# control_board_final.net
KiCad netlist of a schematic drawn in EAGLE
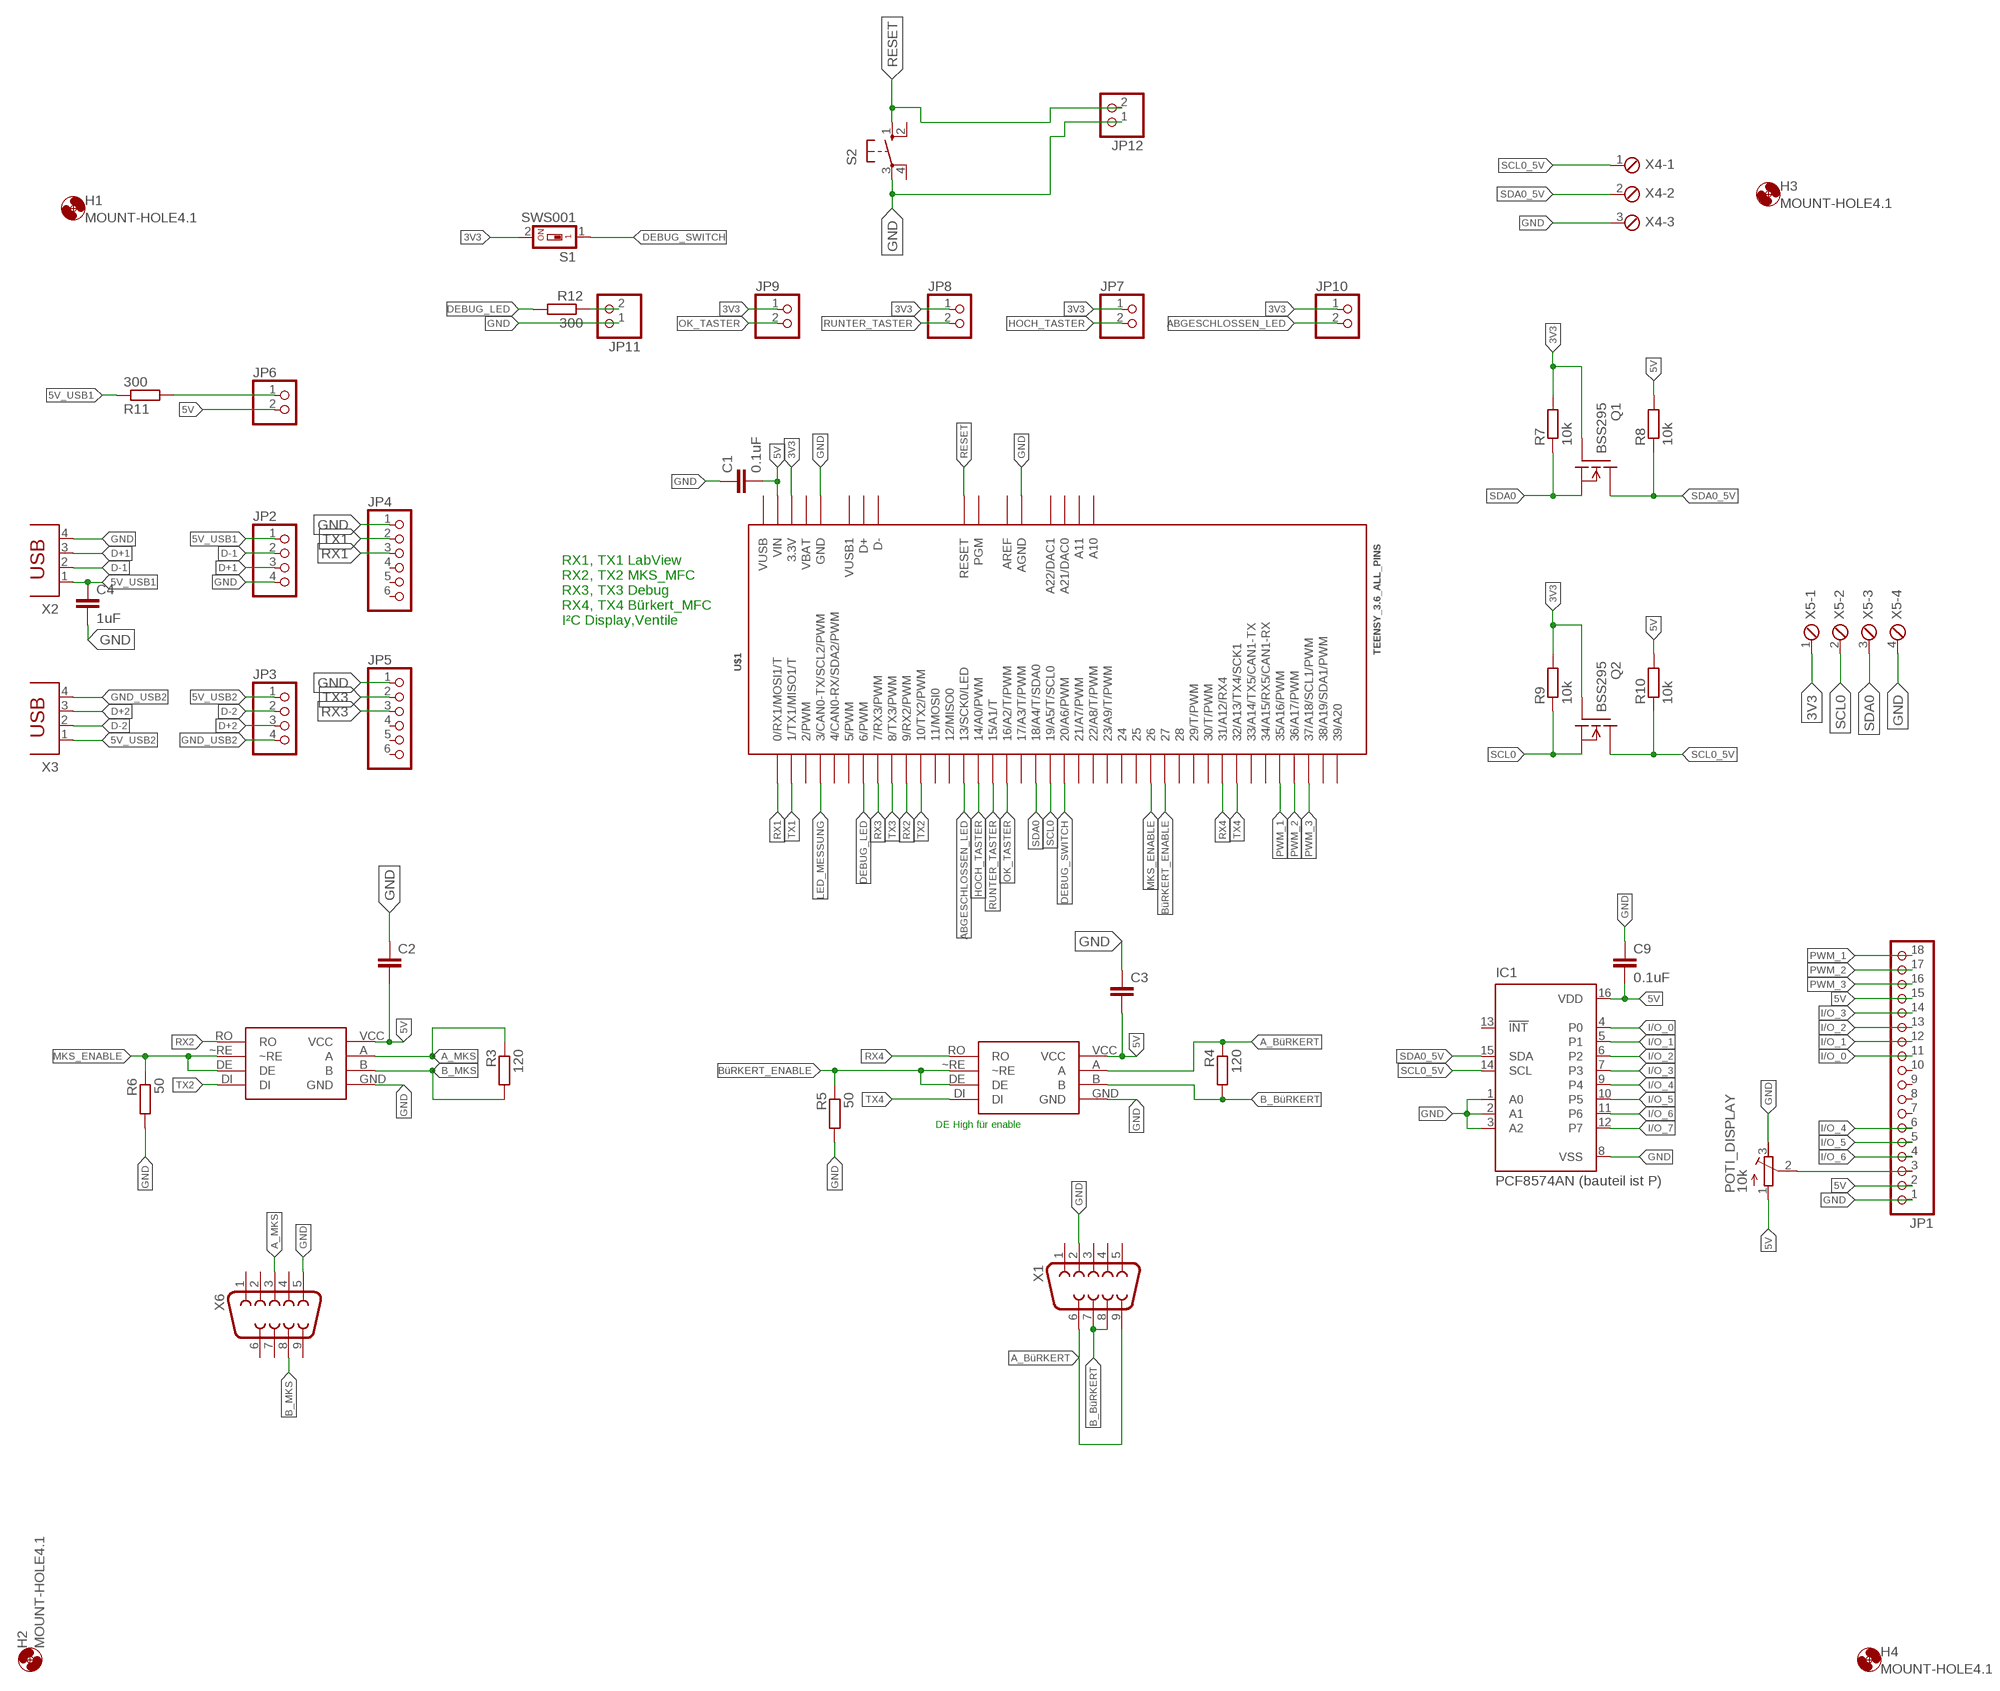
[diagram p0: schematic, sheet 1]

(export (version "E")
  (design (tool "Eeschema 10.0.6"))
  (components
    (comp (ref "C1")
      (value "0.1uF")
      (footprint "eagle-import:C0805")
      (libsource (lib "eagle-import") (part "C-EUC0805"))
    )
    (comp (ref "C2")
      (value "C-EUC0805")
      (footprint "eagle-import:C0805")
      (libsource (lib "eagle-import") (part "C-EUC0805"))
    )
    (comp (ref "C3")
      (value "C-EUC0805")
      (footprint "eagle-import:C0805")
      (libsource (lib "eagle-import") (part "C-EUC0805"))
    )
    (comp (ref "C4")
      (value "1uF")
      (footprint "eagle-import:C0805")
      (libsource (lib "eagle-import") (part "C-EUC0805"))
    )
    (comp (ref "C9")
      (value "0.1uF")
      (footprint "eagle-import:C0805")
      (libsource (lib "eagle-import") (part "C-EUC0805"))
    )
    (comp (ref "H1")
      (value "MOUNT-HOLE4.1")
      (footprint "eagle-import:4,1")
      (libsource (lib "eagle-import") (part "MOUNT-HOLE4.1"))
    )
    (comp (ref "H2")
      (value "MOUNT-HOLE4.1")
      (footprint "eagle-import:4,1")
      (libsource (lib "eagle-import") (part "MOUNT-HOLE4.1"))
    )
    (comp (ref "H3")
      (value "MOUNT-HOLE4.1")
      (footprint "eagle-import:4,1")
      (libsource (lib "eagle-import") (part "MOUNT-HOLE4.1"))
    )
    (comp (ref "H4")
      (value "MOUNT-HOLE4.1")
      (footprint "eagle-import:4,1")
      (libsource (lib "eagle-import") (part "MOUNT-HOLE4.1"))
    )
    (comp (ref "IC1")
      (value "PCF8574AN (bauteil ist P)")
      (footprint "eagle-import:DIL16")
      (fields (field (name "MPN") "PCF8574PN"))
      (libsource (lib "eagle-import") (part "PCF8574P"))
    )
    (comp (ref "JP1")
      (value "PINHD-1X18")
      (footprint "eagle-import:1X18")
      (libsource (lib "eagle-import") (part "PINHD-1X18"))
    )
    (comp (ref "JP2")
      (value "PINHD-1X4")
      (footprint "eagle-import:1X04")
      (libsource (lib "eagle-import") (part "PINHD-1X4"))
    )
    (comp (ref "JP3")
      (value "PINHD-1X4")
      (footprint "eagle-import:1X04")
      (libsource (lib "eagle-import") (part "PINHD-1X4"))
    )
    (comp (ref "JP4")
      (value "PINHD-1X6")
      (footprint "eagle-import:1X06")
      (libsource (lib "eagle-import") (part "PINHD-1X6"))
    )
    (comp (ref "JP5")
      (value "PINHD-1X6")
      (footprint "eagle-import:1X06")
      (libsource (lib "eagle-import") (part "PINHD-1X6"))
    )
    (comp (ref "JP6")
      (value "PINHD-1X2")
      (footprint "eagle-import:1X02")
      (libsource (lib "eagle-import") (part "PINHD-1X2"))
    )
    (comp (ref "JP7")
      (value "PINHD-1X2")
      (footprint "eagle-import:1X02")
      (libsource (lib "eagle-import") (part "PINHD-1X2"))
    )
    (comp (ref "JP8")
      (value "PINHD-1X2")
      (footprint "eagle-import:1X02")
      (libsource (lib "eagle-import") (part "PINHD-1X2"))
    )
    (comp (ref "JP9")
      (value "PINHD-1X2")
      (footprint "eagle-import:1X02")
      (libsource (lib "eagle-import") (part "PINHD-1X2"))
    )
    (comp (ref "JP10")
      (value "PINHD-1X2")
      (footprint "eagle-import:1X02")
      (libsource (lib "eagle-import") (part "PINHD-1X2"))
    )
    (comp (ref "JP11")
      (value "PINHD-1X2")
      (footprint "eagle-import:1X02")
      (libsource (lib "eagle-import") (part "PINHD-1X2"))
    )
    (comp (ref "JP12")
      (value "PINHD-1X2")
      (footprint "eagle-import:1X02")
      (libsource (lib "eagle-import") (part "PINHD-1X2"))
    )
    (comp (ref "POTI_DISPLAY")
      (value "10k")
      (footprint "eagle-import:RTRIM3374")
      (libsource (lib "eagle-import") (part "R-TRIMM3374"))
    )
    (comp (ref "Q1")
      (value "BSS295")
      (footprint "eagle-import:TO92")
      (libsource (lib "eagle-import") (part "BSS295"))
    )
    (comp (ref "Q2")
      (value "BSS295")
      (footprint "eagle-import:TO92")
      (libsource (lib "eagle-import") (part "BSS295"))
    )
    (comp (ref "R3")
      (value "120")
      (footprint "eagle-import:R0805")
      (libsource (lib "eagle-import") (part "R-EU_R0805"))
    )
    (comp (ref "R4")
      (value "120")
      (footprint "eagle-import:R0805")
      (libsource (lib "eagle-import") (part "R-EU_R0805"))
    )
    (comp (ref "R5")
      (value "50")
      (footprint "eagle-import:R0805")
      (libsource (lib "eagle-import") (part "R-EU_R0805"))
    )
    (comp (ref "R6")
      (value "50")
      (footprint "eagle-import:R0805")
      (libsource (lib "eagle-import") (part "R-EU_R0805"))
    )
    (comp (ref "R7")
      (value "10k")
      (footprint "eagle-import:VMTA55")
      (libsource (lib "eagle-import") (part "R-EU_VMTA55"))
    )
    (comp (ref "R8")
      (value "10k")
      (footprint "eagle-import:VMTA55")
      (libsource (lib "eagle-import") (part "R-EU_VMTA55"))
    )
    (comp (ref "R9")
      (value "10k")
      (footprint "eagle-import:VMTA55")
      (libsource (lib "eagle-import") (part "R-EU_VMTA55"))
    )
    (comp (ref "R10")
      (value "10k")
      (footprint "eagle-import:VMTA55")
      (libsource (lib "eagle-import") (part "R-EU_VMTA55"))
    )
    (comp (ref "R11")
      (value "300")
      (footprint "eagle-import:R0805")
      (libsource (lib "eagle-import") (part "R-EU_R0805"))
    )
    (comp (ref "R12")
      (value "300")
      (footprint "eagle-import:R0805")
      (libsource (lib "eagle-import") (part "R-EU_R0805"))
    )
    (comp (ref "S1")
      (value "SWS001")
      (footprint "eagle-import:SMS-001")
      (libsource (lib "eagle-import") (part "SWS001"))
    )
    (comp (ref "S2")
      (value "10-XX")
      (footprint "eagle-import:B3F-10XX")
      (fields (field (name "MPN") "B3F-1000"))
      (libsource (lib "eagle-import") (part "10-XX"))
    )
    (comp (ref "U$1")
      (value "TEENSY_3.6_ALL_PINS")
      (footprint "eagle-import:TEENSY_3.6_ALL_PINS")
      (libsource (lib "eagle-import") (part "TEENSY_3.6_ALL_PINS"))
    )
    (comp (ref "U$5")
      (value "MAX14775EASA+")
      (footprint "eagle-import:SO08")
      (libsource (lib "eagle-import") (part "MAX14775EASA+"))
    )
    (comp (ref "U$6")
      (value "MAX14775EASA+")
      (footprint "eagle-import:SO08")
      (libsource (lib "eagle-import") (part "MAX14775EASA+"))
    )
    (comp (ref "X1")
      (value "F09HP")
      (footprint "eagle-import:F09HP")
      (libsource (lib "eagle-import") (part "F09HP"))
    )
    (comp (ref "X2")
      (value "PN61729")
      (footprint "eagle-import:PN61729")
      (libsource (lib "eagle-import") (part "PN61729"))
    )
    (comp (ref "X3")
      (value "PN61729")
      (footprint "eagle-import:PN61729")
      (libsource (lib "eagle-import") (part "PN61729"))
    )
    (comp (ref "X4")
      (value "MPT3")
      (footprint "eagle-import:3POL254")
      (libsource (lib "eagle-import") (part "MPT3"))
    )
    (comp (ref "X5")
      (value "MPT4")
      (footprint "eagle-import:4POL254")
      (libsource (lib "eagle-import") (part "MPT4"))
    )
    (comp (ref "X6")
      (value "F09HP")
      (footprint "eagle-import:F09HP")
      (libsource (lib "eagle-import") (part "F09HP"))
    )
  )
  (nets
    (net (code "1") (name "/AREF") (class "Default")
      (node (ref "U$1") (pin "AREF") (pinfunction "AREF_AREF") (pintype "power_in"))
    )
    (net (code "2") (name "/VBAT") (class "Default")
      (node (ref "U$1") (pin "VBAT") (pinfunction "VBAT_VBAT") (pintype "power_in"))
    )
    (net (code "3") (name "/VUSB") (class "Default")
      (node (ref "U$1") (pin "VUSB") (pinfunction "VUSB_VUSB") (pintype "power_in"))
    )
    (net (code "4") (name "/VUSB1") (class "Default")
      (node (ref "U$1") (pin "VUSB1") (pinfunction "VUSB1_VUSB1") (pintype "power_in"))
    )
    (net (code "5") (name "3V3") (class "Default")
      (node (ref "JP10") (pin "1") (pinfunction "1_1") (pintype "passive"))
      (node (ref "JP7") (pin "1") (pinfunction "1_1") (pintype "passive"))
      (node (ref "JP8") (pin "1") (pinfunction "1_1") (pintype "passive"))
      (node (ref "JP9") (pin "1") (pinfunction "1_1") (pintype "passive"))
      (node (ref "Q1") (pin "1") (pinfunction "G_1") (pintype "passive"))
      (node (ref "Q2") (pin "1") (pinfunction "G_1") (pintype "passive"))
      (node (ref "R7") (pin "2") (pinfunction "2_2") (pintype "passive"))
      (node (ref "R9") (pin "2") (pinfunction "2_2") (pintype "passive"))
      (node (ref "S1") (pin "2") (pinfunction "2_2") (pintype "passive"))
      (node (ref "U$1") (pin "3.3V") (pinfunction "3.3V_3.3V") (pintype "power_in"))
      (node (ref "U$1") (pin "3.3V3") (pinfunction "3.3V_3.3V3") (pintype "power_in"))
      (node (ref "U$1") (pin "3.3V4") (pinfunction "3.3V_3.3V4") (pintype "power_in"))
      (node (ref "X5") (pin "1") (pinfunction "1_1") (pintype "passive"))
    )
    (net (code "6") (name "5V") (class "Default")
      (node (ref "C1") (pin "2") (pinfunction "2_2") (pintype "passive"))
      (node (ref "C2") (pin "2") (pinfunction "2_2") (pintype "passive"))
      (node (ref "C3") (pin "2") (pinfunction "2_2") (pintype "passive"))
      (node (ref "C9") (pin "2") (pinfunction "2_2") (pintype "passive"))
      (node (ref "IC1") (pin "16") (pinfunction "VDD_16") (pintype "power_in"))
      (node (ref "JP1") (pin "15") (pinfunction "15_15") (pintype "passive"))
      (node (ref "JP1") (pin "2") (pinfunction "2_2") (pintype "passive"))
      (node (ref "JP6") (pin "2") (pinfunction "2_2") (pintype "passive"))
      (node (ref "POTI_DISPLAY") (pin "1") (pinfunction "A_1") (pintype "passive"))
      (node (ref "R10") (pin "2") (pinfunction "2_2") (pintype "passive"))
      (node (ref "R8") (pin "2") (pinfunction "2_2") (pintype "passive"))
      (node (ref "U$1") (pin "VIN") (pinfunction "VIN_VIN") (pintype "power_in"))
      (node (ref "U$5") (pin "VCC") (pinfunction "VCC_VCC") (pintype "bidirectional"))
      (node (ref "U$6") (pin "VCC") (pinfunction "VCC_VCC") (pintype "bidirectional"))
    )
    (net (code "7") (name "5V_USB1") (class "Default")
      (node (ref "C4") (pin "1") (pinfunction "1_1") (pintype "passive"))
      (node (ref "JP2") (pin "1") (pinfunction "1_1") (pintype "passive"))
      (node (ref "R11") (pin "1") (pinfunction "1_1") (pintype "passive"))
      (node (ref "X2") (pin "1") (pinfunction "1_1") (pintype "passive"))
    )
    (net (code "8") (name "5V_USB2") (class "Default")
      (node (ref "JP3") (pin "1") (pinfunction "1_1") (pintype "passive"))
      (node (ref "X3") (pin "1") (pinfunction "1_1") (pintype "passive"))
    )
    (net (code "9") (name "ABGESCHLOSSEN_LED") (class "Default")
      (node (ref "JP10") (pin "2") (pinfunction "2_2") (pintype "passive"))
      (node (ref "U$1") (pin "13") (pinfunction "13/SCK0/LED_13") (pintype "bidirectional"))
    )
    (net (code "10") (name "A_BüRKERT") (class "Default")
      (node (ref "R4") (pin "1") (pinfunction "1_1") (pintype "passive"))
      (node (ref "U$5") (pin "A") (pinfunction "A_A") (pintype "bidirectional"))
      (node (ref "X1") (pin "6") (pinfunction "6_6") (pintype "passive"))
      (node (ref "X1") (pin "9") (pinfunction "9_9") (pintype "passive"))
    )
    (net (code "11") (name "A_MKS") (class "Default")
      (node (ref "R3") (pin "1") (pinfunction "1_1") (pintype "passive"))
      (node (ref "U$6") (pin "A") (pinfunction "A_A") (pintype "bidirectional"))
      (node (ref "X6") (pin "3") (pinfunction "3_3") (pintype "passive"))
    )
    (net (code "12") (name "B_BüRKERT") (class "Default")
      (node (ref "R4") (pin "2") (pinfunction "2_2") (pintype "passive"))
      (node (ref "U$5") (pin "B") (pinfunction "B_B") (pintype "bidirectional"))
      (node (ref "X1") (pin "7") (pinfunction "7_7") (pintype "passive"))
      (node (ref "X1") (pin "8") (pinfunction "8_8") (pintype "passive"))
    )
    (net (code "13") (name "B_MKS") (class "Default")
      (node (ref "R3") (pin "2") (pinfunction "2_2") (pintype "passive"))
      (node (ref "U$6") (pin "B") (pinfunction "B_B") (pintype "bidirectional"))
      (node (ref "X6") (pin "8") (pinfunction "8_8") (pintype "passive"))
    )
    (net (code "14") (name "BüRKERT_ENABLE") (class "Default")
      (node (ref "R5") (pin "1") (pinfunction "1_1") (pintype "passive"))
      (node (ref "U$1") (pin "27") (pinfunction "27_27") (pintype "bidirectional"))
      (node (ref "U$5") (pin "DE") (pinfunction "DE_DE") (pintype "bidirectional"))
      (node (ref "U$5") (pin "~RE") (pinfunction "~{RE}_~RE") (pintype "bidirectional"))
    )
    (net (code "15") (name "D+1") (class "Default")
      (node (ref "JP2") (pin "3") (pinfunction "3_3") (pintype "passive"))
      (node (ref "X2") (pin "3") (pinfunction "3_3") (pintype "passive"))
    )
    (net (code "16") (name "D+2") (class "Default")
      (node (ref "JP3") (pin "3") (pinfunction "3_3") (pintype "passive"))
      (node (ref "X3") (pin "3") (pinfunction "3_3") (pintype "passive"))
    )
    (net (code "17") (name "D-1") (class "Default")
      (node (ref "JP2") (pin "2") (pinfunction "2_2") (pintype "passive"))
      (node (ref "X2") (pin "2") (pinfunction "2_2") (pintype "passive"))
    )
    (net (code "18") (name "D-2") (class "Default")
      (node (ref "JP3") (pin "2") (pinfunction "2_2") (pintype "passive"))
      (node (ref "X3") (pin "2") (pinfunction "2_2") (pintype "passive"))
    )
    (net (code "19") (name "DEBUG_LED") (class "Default")
      (node (ref "R12") (pin "2") (pinfunction "2_2") (pintype "passive"))
      (node (ref "U$1") (pin "6") (pinfunction "6/PWM_6") (pintype "bidirectional"))
    )
    (net (code "20") (name "DEBUG_SWITCH") (class "Default")
      (node (ref "S1") (pin "1") (pinfunction "1_1") (pintype "passive"))
      (node (ref "U$1") (pin "20/A6") (pinfunction "20/A6/PWM_20/A6") (pintype "bidirectional"))
    )
    (net (code "21") (name "GND") (class "Default")
      (node (ref "C1") (pin "1") (pinfunction "1_1") (pintype "passive"))
      (node (ref "C2") (pin "1") (pinfunction "1_1") (pintype "passive"))
      (node (ref "C3") (pin "1") (pinfunction "1_1") (pintype "passive"))
      (node (ref "C4") (pin "2") (pinfunction "2_2") (pintype "passive"))
      (node (ref "C9") (pin "1") (pinfunction "1_1") (pintype "passive"))
      (node (ref "IC1") (pin "1") (pinfunction "A0_1") (pintype "input"))
      (node (ref "IC1") (pin "2") (pinfunction "A1_2") (pintype "input"))
      (node (ref "IC1") (pin "3") (pinfunction "A2_3") (pintype "input"))
      (node (ref "IC1") (pin "8") (pinfunction "VSS_8") (pintype "power_in"))
      (node (ref "JP1") (pin "1") (pinfunction "1_1") (pintype "passive"))
      (node (ref "JP11") (pin "1") (pinfunction "1_1") (pintype "passive"))
      (node (ref "JP12") (pin "1") (pinfunction "1_1") (pintype "passive"))
      (node (ref "JP2") (pin "4") (pinfunction "4_4") (pintype "passive"))
      (node (ref "JP4") (pin "1") (pinfunction "1_1") (pintype "passive"))
      (node (ref "JP5") (pin "1") (pinfunction "1_1") (pintype "passive"))
      (node (ref "POTI_DISPLAY") (pin "3") (pinfunction "E_3") (pintype "passive"))
      (node (ref "R5") (pin "2") (pinfunction "2_2") (pintype "passive"))
      (node (ref "R6") (pin "2") (pinfunction "2_2") (pintype "passive"))
      (node (ref "S2") (pin "3") (pinfunction "P_3") (pintype "passive"))
      (node (ref "U$1") (pin "AGND") (pinfunction "AGND_AGND") (pintype "power_in"))
      (node (ref "U$1") (pin "GND") (pinfunction "GND_GND") (pintype "power_in"))
      (node (ref "U$1") (pin "GND1") (pinfunction "GND_GND1") (pintype "power_in"))
      (node (ref "U$1") (pin "GND3") (pinfunction "GND_GND3") (pintype "power_in"))
      (node (ref "U$1") (pin "GND4") (pinfunction "GND_GND4") (pintype "power_in"))
      (node (ref "U$1") (pin "GND6") (pinfunction "GND_GND6") (pintype "power_in"))
      (node (ref "U$5") (pin "GND") (pinfunction "GND_GND") (pintype "bidirectional"))
      (node (ref "U$6") (pin "GND") (pinfunction "GND_GND") (pintype "bidirectional"))
      (node (ref "X1") (pin "2") (pinfunction "2_2") (pintype "passive"))
      (node (ref "X2") (pin "4") (pinfunction "4_4") (pintype "passive"))
      (node (ref "X4") (pin "3") (pinfunction "1_3") (pintype "passive"))
      (node (ref "X5") (pin "4") (pinfunction "1_4") (pintype "passive"))
      (node (ref "X6") (pin "5") (pinfunction "5_5") (pintype "passive"))
    )
    (net (code "22") (name "GND_USB2") (class "Default")
      (node (ref "JP3") (pin "4") (pinfunction "4_4") (pintype "passive"))
      (node (ref "X3") (pin "4") (pinfunction "4_4") (pintype "passive"))
    )
    (net (code "23") (name "HOCH_TASTER") (class "Default")
      (node (ref "JP7") (pin "2") (pinfunction "2_2") (pintype "passive"))
      (node (ref "U$1") (pin "14/A0") (pinfunction "14/A0/PWM_14/A0") (pintype "bidirectional"))
    )
    (net (code "24") (name "I{slash}O_0") (class "Default")
      (node (ref "IC1") (pin "4") (pinfunction "P0_4") (pintype "bidirectional"))
      (node (ref "JP1") (pin "11") (pinfunction "11_11") (pintype "passive"))
    )
    (net (code "25") (name "I{slash}O_1") (class "Default")
      (node (ref "IC1") (pin "5") (pinfunction "P1_5") (pintype "bidirectional"))
      (node (ref "JP1") (pin "12") (pinfunction "12_12") (pintype "passive"))
    )
    (net (code "26") (name "I{slash}O_2") (class "Default")
      (node (ref "IC1") (pin "6") (pinfunction "P2_6") (pintype "bidirectional"))
      (node (ref "JP1") (pin "13") (pinfunction "13_13") (pintype "passive"))
    )
    (net (code "27") (name "I{slash}O_3") (class "Default")
      (node (ref "IC1") (pin "7") (pinfunction "P3_7") (pintype "bidirectional"))
      (node (ref "JP1") (pin "14") (pinfunction "14_14") (pintype "passive"))
    )
    (net (code "28") (name "I{slash}O_4") (class "Default")
      (node (ref "IC1") (pin "9") (pinfunction "P4_9") (pintype "bidirectional"))
      (node (ref "JP1") (pin "6") (pinfunction "6_6") (pintype "passive"))
    )
    (net (code "29") (name "I{slash}O_5") (class "Default")
      (node (ref "IC1") (pin "10") (pinfunction "P5_10") (pintype "bidirectional"))
      (node (ref "JP1") (pin "5") (pinfunction "5_5") (pintype "passive"))
    )
    (net (code "30") (name "I{slash}O_6") (class "Default")
      (node (ref "IC1") (pin "11") (pinfunction "P6_11") (pintype "bidirectional"))
      (node (ref "JP1") (pin "4") (pinfunction "4_4") (pintype "passive"))
    )
    (net (code "31") (name "I{slash}O_7") (class "Default")
      (node (ref "IC1") (pin "12") (pinfunction "P7_12") (pintype "bidirectional"))
    )
    (net (code "32") (name "LED_MESSUNG") (class "Default")
      (node (ref "U$1") (pin "3") (pinfunction "3/CAN0-TX/SCL2/PWM_3") (pintype "bidirectional"))
    )
    (net (code "33") (name "MKS_ENABLE") (class "Default")
      (node (ref "R6") (pin "1") (pinfunction "1_1") (pintype "passive"))
      (node (ref "U$1") (pin "26") (pinfunction "26_26") (pintype "bidirectional"))
      (node (ref "U$6") (pin "DE") (pinfunction "DE_DE") (pintype "bidirectional"))
      (node (ref "U$6") (pin "~RE") (pinfunction "~{RE}_~RE") (pintype "bidirectional"))
    )
    (net (code "34") (name "Net-(JP6-Pad1)") (class "Default")
      (node (ref "JP6") (pin "1") (pinfunction "1_1") (pintype "passive"))
      (node (ref "R11") (pin "2") (pinfunction "2_2") (pintype "passive"))
    )
    (net (code "35") (name "Net-(JP11-Pad2)") (class "Default")
      (node (ref "JP11") (pin "2") (pinfunction "2_2") (pintype "passive"))
      (node (ref "R12") (pin "1") (pinfunction "1_1") (pintype "passive"))
    )
    (net (code "36") (name "Net-(POTI_DISPLAY-S)") (class "Default")
      (node (ref "JP1") (pin "3") (pinfunction "3_3") (pintype "passive"))
      (node (ref "POTI_DISPLAY") (pin "2") (pinfunction "S_2") (pintype "passive"))
    )
    (net (code "37") (name "OK_TASTER") (class "Default")
      (node (ref "JP9") (pin "2") (pinfunction "2_2") (pintype "passive"))
      (node (ref "U$1") (pin "16/A2") (pinfunction "16/A2/T/PWM_16/A2") (pintype "bidirectional"))
    )
    (net (code "38") (name "PWM_1") (class "Default")
      (node (ref "JP1") (pin "18") (pinfunction "18_18") (pintype "passive"))
      (node (ref "U$1") (pin "35/A16") (pinfunction "35/A16/PWM_35/A16") (pintype "bidirectional"))
    )
    (net (code "39") (name "PWM_2") (class "Default")
      (node (ref "JP1") (pin "17") (pinfunction "17_17") (pintype "passive"))
      (node (ref "U$1") (pin "36/A17") (pinfunction "36/A17/PWM_36/A17") (pintype "bidirectional"))
    )
    (net (code "40") (name "PWM_3") (class "Default")
      (node (ref "JP1") (pin "16") (pinfunction "16_16") (pintype "passive"))
      (node (ref "U$1") (pin "37/A18") (pinfunction "37/A18/SCL1/PWM_37/A18") (pintype "bidirectional"))
    )
    (net (code "41") (name "RESET") (class "Default")
      (node (ref "JP12") (pin "2") (pinfunction "2_2") (pintype "passive"))
      (node (ref "S2") (pin "1") (pinfunction "S_1") (pintype "passive"))
      (node (ref "U$1") (pin "RESET") (pinfunction "RESET_RESET") (pintype "bidirectional"))
    )
    (net (code "42") (name "RUNTER_TASTER") (class "Default")
      (node (ref "JP8") (pin "2") (pinfunction "2_2") (pintype "passive"))
      (node (ref "U$1") (pin "15/A1") (pinfunction "15/A1/T_15/A1") (pintype "bidirectional"))
    )
    (net (code "43") (name "RX1") (class "Default")
      (node (ref "JP4") (pin "3") (pinfunction "3_3") (pintype "passive"))
      (node (ref "U$1") (pin "0") (pinfunction "0/RX1/MOSI1/T_0") (pintype "bidirectional"))
    )
    (net (code "44") (name "RX2") (class "Default")
      (node (ref "U$1") (pin "9") (pinfunction "9/RX2/PWM_9") (pintype "bidirectional"))
      (node (ref "U$6") (pin "RO") (pinfunction "RO_RO") (pintype "bidirectional"))
    )
    (net (code "45") (name "RX3") (class "Default")
      (node (ref "JP5") (pin "3") (pinfunction "3_3") (pintype "passive"))
      (node (ref "U$1") (pin "7") (pinfunction "7/RX3/PWM_7") (pintype "bidirectional"))
    )
    (net (code "46") (name "RX4") (class "Default")
      (node (ref "U$1") (pin "31/A12") (pinfunction "31/A12/RX4_31/A12") (pintype "bidirectional"))
      (node (ref "U$5") (pin "RO") (pinfunction "RO_RO") (pintype "bidirectional"))
    )
    (net (code "47") (name "SCL0") (class "Default")
      (node (ref "Q2") (pin "3") (pinfunction "S_3") (pintype "passive"))
      (node (ref "R9") (pin "1") (pinfunction "1_1") (pintype "passive"))
      (node (ref "U$1") (pin "19/A5") (pinfunction "19/A5/T/SCL0_19/A5") (pintype "bidirectional"))
      (node (ref "X5") (pin "2") (pinfunction "1_2") (pintype "passive"))
    )
    (net (code "48") (name "SCL0_5V") (class "Default")
      (node (ref "IC1") (pin "14") (pinfunction "SCL_14") (pintype "input"))
      (node (ref "Q2") (pin "2") (pinfunction "D_2") (pintype "passive"))
      (node (ref "R10") (pin "1") (pinfunction "1_1") (pintype "passive"))
      (node (ref "X4") (pin "1") (pinfunction "1_1") (pintype "passive"))
    )
    (net (code "49") (name "SDA0") (class "Default")
      (node (ref "Q1") (pin "3") (pinfunction "S_3") (pintype "passive"))
      (node (ref "R7") (pin "1") (pinfunction "1_1") (pintype "passive"))
      (node (ref "U$1") (pin "18/A4") (pinfunction "18/A4/T/SDA0_18/A4") (pintype "bidirectional"))
      (node (ref "X5") (pin "3") (pinfunction "1_3") (pintype "passive"))
    )
    (net (code "50") (name "SDA0_5V") (class "Default")
      (node (ref "IC1") (pin "15") (pinfunction "SDA_15") (pintype "bidirectional"))
      (node (ref "Q1") (pin "2") (pinfunction "D_2") (pintype "passive"))
      (node (ref "R8") (pin "1") (pinfunction "1_1") (pintype "passive"))
      (node (ref "X4") (pin "2") (pinfunction "1_2") (pintype "passive"))
    )
    (net (code "51") (name "TX1") (class "Default")
      (node (ref "JP4") (pin "2") (pinfunction "2_2") (pintype "passive"))
      (node (ref "U$1") (pin "1") (pinfunction "1/TX1/MISO1/T_1") (pintype "bidirectional"))
    )
    (net (code "52") (name "TX2") (class "Default")
      (node (ref "U$1") (pin "10") (pinfunction "10/TX2/PWM_10") (pintype "bidirectional"))
      (node (ref "U$6") (pin "DI") (pinfunction "DI_DI") (pintype "bidirectional"))
    )
    (net (code "53") (name "TX3") (class "Default")
      (node (ref "JP5") (pin "2") (pinfunction "2_2") (pintype "passive"))
      (node (ref "U$1") (pin "8") (pinfunction "8/TX3/PWM_8") (pintype "bidirectional"))
    )
    (net (code "54") (name "TX4") (class "Default")
      (node (ref "U$1") (pin "32/A13") (pinfunction "32/A13/TX4/SCK1_32/A13") (pintype "bidirectional"))
      (node (ref "U$5") (pin "DI") (pinfunction "DI_DI") (pintype "bidirectional"))
    )
    (net (code "55") (name "unconnected-(IC1-~{INT}-Pad13)") (class "Default")
      (node (ref "IC1") (pin "13") (pinfunction "~{INT}_13") (pintype "output"))
    )
    (net (code "56") (name "unconnected-(JP1-Pad7)") (class "Default")
      (node (ref "JP1") (pin "7") (pinfunction "7_7") (pintype "passive"))
    )
    (net (code "57") (name "unconnected-(JP1-Pad8)") (class "Default")
      (node (ref "JP1") (pin "8") (pinfunction "8_8") (pintype "passive"))
    )
    (net (code "58") (name "unconnected-(JP1-Pad9)") (class "Default")
      (node (ref "JP1") (pin "9") (pinfunction "9_9") (pintype "passive"))
    )
    (net (code "59") (name "unconnected-(JP1-Pad10)") (class "Default")
      (node (ref "JP1") (pin "10") (pinfunction "10_10") (pintype "passive"))
    )
    (net (code "60") (name "unconnected-(JP4-Pad4)") (class "Default")
      (node (ref "JP4") (pin "4") (pinfunction "4_4") (pintype "passive"))
    )
    (net (code "61") (name "unconnected-(JP4-Pad5)") (class "Default")
      (node (ref "JP4") (pin "5") (pinfunction "5_5") (pintype "passive"))
    )
    (net (code "62") (name "unconnected-(JP4-Pad6)") (class "Default")
      (node (ref "JP4") (pin "6") (pinfunction "6_6") (pintype "passive"))
    )
    (net (code "63") (name "unconnected-(JP5-Pad4)") (class "Default")
      (node (ref "JP5") (pin "4") (pinfunction "4_4") (pintype "passive"))
    )
    (net (code "64") (name "unconnected-(JP5-Pad5)") (class "Default")
      (node (ref "JP5") (pin "5") (pinfunction "5_5") (pintype "passive"))
    )
    (net (code "65") (name "unconnected-(JP5-Pad6)") (class "Default")
      (node (ref "JP5") (pin "6") (pinfunction "6_6") (pintype "passive"))
    )
    (net (code "66") (name "unconnected-(S2-P1-Pad4)") (class "Default")
      (node (ref "S2") (pin "4") (pinfunction "P1_4") (pintype "passive"))
    )
    (net (code "67") (name "unconnected-(S2-S1-Pad2)") (class "Default")
      (node (ref "S2") (pin "2") (pinfunction "S1_2") (pintype "passive"))
    )
    (net (code "68") (name "unconnected-(U$1-2{slash}PWM-Pad2)") (class "Default")
      (node (ref "U$1") (pin "2") (pinfunction "2/PWM_2") (pintype "bidirectional"))
    )
    (net (code "69") (name "unconnected-(U$1-4{slash}CAN0-RX{slash}SDA2{slash}PWM-Pad4)") (class "Default")
      (node (ref "U$1") (pin "4") (pinfunction "4/CAN0-RX/SDA2/PWM_4") (pintype "bidirectional"))
    )
    (net (code "70") (name "unconnected-(U$1-5{slash}PWM-Pad5)") (class "Default")
      (node (ref "U$1") (pin "5") (pinfunction "5/PWM_5") (pintype "bidirectional"))
    )
    (net (code "71") (name "unconnected-(U$1-11{slash}MOSI0-Pad11)") (class "Default")
      (node (ref "U$1") (pin "11") (pinfunction "11/MOSI0_11") (pintype "bidirectional"))
    )
    (net (code "72") (name "unconnected-(U$1-12{slash}MISO0-Pad12)") (class "Default")
      (node (ref "U$1") (pin "12") (pinfunction "12/MISO0_12") (pintype "bidirectional"))
    )
    (net (code "73") (name "unconnected-(U$1-17{slash}A3{slash}T{slash}PWM-Pad17{slash}A3)") (class "Default")
      (node (ref "U$1") (pin "17/A3") (pinfunction "17/A3/T/PWM_17/A3") (pintype "bidirectional"))
    )
    (net (code "74") (name "unconnected-(U$1-21{slash}A7{slash}PWM-Pad21{slash}A7)") (class "Default")
      (node (ref "U$1") (pin "21/A7") (pinfunction "21/A7/PWM_21/A7") (pintype "bidirectional"))
    )
    (net (code "75") (name "unconnected-(U$1-22{slash}A8{slash}T{slash}PWM-Pad22{slash}A8)") (class "Default")
      (node (ref "U$1") (pin "22/A8") (pinfunction "22/A8/T/PWM_22/A8") (pintype "bidirectional"))
    )
    (net (code "76") (name "unconnected-(U$1-23{slash}A9{slash}T{slash}PWM-Pad23{slash}A9)") (class "Default")
      (node (ref "U$1") (pin "23/A9") (pinfunction "23/A9/T/PWM_23/A9") (pintype "bidirectional"))
    )
    (net (code "77") (name "unconnected-(U$1-29{slash}T{slash}PWM-Pad29)") (class "Default")
      (node (ref "U$1") (pin "29") (pinfunction "29/T/PWM_29") (pintype "bidirectional"))
    )
    (net (code "78") (name "unconnected-(U$1-30{slash}T{slash}PWM-Pad30)") (class "Default")
      (node (ref "U$1") (pin "30") (pinfunction "30/T/PWM_30") (pintype "bidirectional"))
    )
    (net (code "79") (name "unconnected-(U$1-33{slash}A14{slash}TX5{slash}CAN1-TX-Pad33{slash}A14)") (class "Default")
      (node (ref "U$1") (pin "33/A14") (pinfunction "33/A14/TX5/CAN1-TX_33/A14") (pintype "bidirectional"))
    )
    (net (code "80") (name "unconnected-(U$1-34{slash}A15{slash}RX5{slash}CAN1-RX-Pad34{slash}A15)") (class "Default")
      (node (ref "U$1") (pin "34/A15") (pinfunction "34/A15/RX5/CAN1-RX_34/A15") (pintype "bidirectional"))
    )
    (net (code "81") (name "unconnected-(U$1-38{slash}A19{slash}SDA1{slash}PWM-Pad38{slash}A19)") (class "Default")
      (node (ref "U$1") (pin "38/A19") (pinfunction "38/A19/SDA1/PWM_38/A19") (pintype "bidirectional"))
    )
    (net (code "82") (name "unconnected-(U$1-A21{slash}DAC0-PadA21)") (class "Default")
      (node (ref "U$1") (pin "A21") (pinfunction "A21/DAC0_A21") (pintype "bidirectional"))
    )
    (net (code "83") (name "unconnected-(U$1-A22{slash}DAC1-PadA22)") (class "Default")
      (node (ref "U$1") (pin "A22") (pinfunction "A22/DAC1_A22") (pintype "bidirectional"))
    )
    (net (code "84") (name "unconnected-(U$1-Pad24)") (class "Default")
      (node (ref "U$1") (pin "24") (pinfunction "24_24") (pintype "bidirectional"))
    )
    (net (code "85") (name "unconnected-(U$1-Pad25)") (class "Default")
      (node (ref "U$1") (pin "25") (pinfunction "25_25") (pintype "bidirectional"))
    )
    (net (code "86") (name "unconnected-(U$1-Pad28)") (class "Default")
      (node (ref "U$1") (pin "28") (pinfunction "28_28") (pintype "bidirectional"))
    )
    (net (code "87") (name "unconnected-(U$1-Pad39{slash}A20)") (class "Default")
      (node (ref "U$1") (pin "39/A20") (pinfunction "39/A20_39/A20") (pintype "bidirectional"))
    )
    (net (code "88") (name "unconnected-(U$1-PadA10)") (class "Default")
      (node (ref "U$1") (pin "A10") (pinfunction "A10_A10") (pintype "bidirectional"))
    )
    (net (code "89") (name "unconnected-(U$1-PadA11)") (class "Default")
      (node (ref "U$1") (pin "A11") (pinfunction "A11_A11") (pintype "bidirectional"))
    )
    (net (code "90") (name "unconnected-(U$1-PadD+)") (class "Default")
      (node (ref "U$1") (pin "D+") (pinfunction "D+_D+") (pintype "bidirectional"))
    )
    (net (code "91") (name "unconnected-(U$1-PadD-)") (class "Default")
      (node (ref "U$1") (pin "D-") (pinfunction "D-_D-") (pintype "bidirectional"))
    )
    (net (code "92") (name "unconnected-(U$1-PadPGM)") (class "Default")
      (node (ref "U$1") (pin "PGM") (pinfunction "PGM_PGM") (pintype "bidirectional"))
    )
    (net (code "93") (name "unconnected-(X1-Pad1)") (class "Default")
      (node (ref "X1") (pin "1") (pinfunction "1_1") (pintype "passive"))
    )
    (net (code "94") (name "unconnected-(X1-Pad3)") (class "Default")
      (node (ref "X1") (pin "3") (pinfunction "3_3") (pintype "passive"))
    )
    (net (code "95") (name "unconnected-(X1-Pad4)") (class "Default")
      (node (ref "X1") (pin "4") (pinfunction "4_4") (pintype "passive"))
    )
    (net (code "96") (name "unconnected-(X1-Pad5)") (class "Default")
      (node (ref "X1") (pin "5") (pinfunction "5_5") (pintype "passive"))
    )
    (net (code "97") (name "unconnected-(X6-Pad1)") (class "Default")
      (node (ref "X6") (pin "1") (pinfunction "1_1") (pintype "passive"))
    )
    (net (code "98") (name "unconnected-(X6-Pad2)") (class "Default")
      (node (ref "X6") (pin "2") (pinfunction "2_2") (pintype "passive"))
    )
    (net (code "99") (name "unconnected-(X6-Pad4)") (class "Default")
      (node (ref "X6") (pin "4") (pinfunction "4_4") (pintype "passive"))
    )
    (net (code "100") (name "unconnected-(X6-Pad6)") (class "Default")
      (node (ref "X6") (pin "6") (pinfunction "6_6") (pintype "passive"))
    )
    (net (code "101") (name "unconnected-(X6-Pad7)") (class "Default")
      (node (ref "X6") (pin "7") (pinfunction "7_7") (pintype "passive"))
    )
    (net (code "102") (name "unconnected-(X6-Pad9)") (class "Default")
      (node (ref "X6") (pin "9") (pinfunction "9_9") (pintype "passive"))
    )
  )
)
